# USB_HUB_schematic.net
KiCad netlist of a schematic drawn in EasyEDA Pro
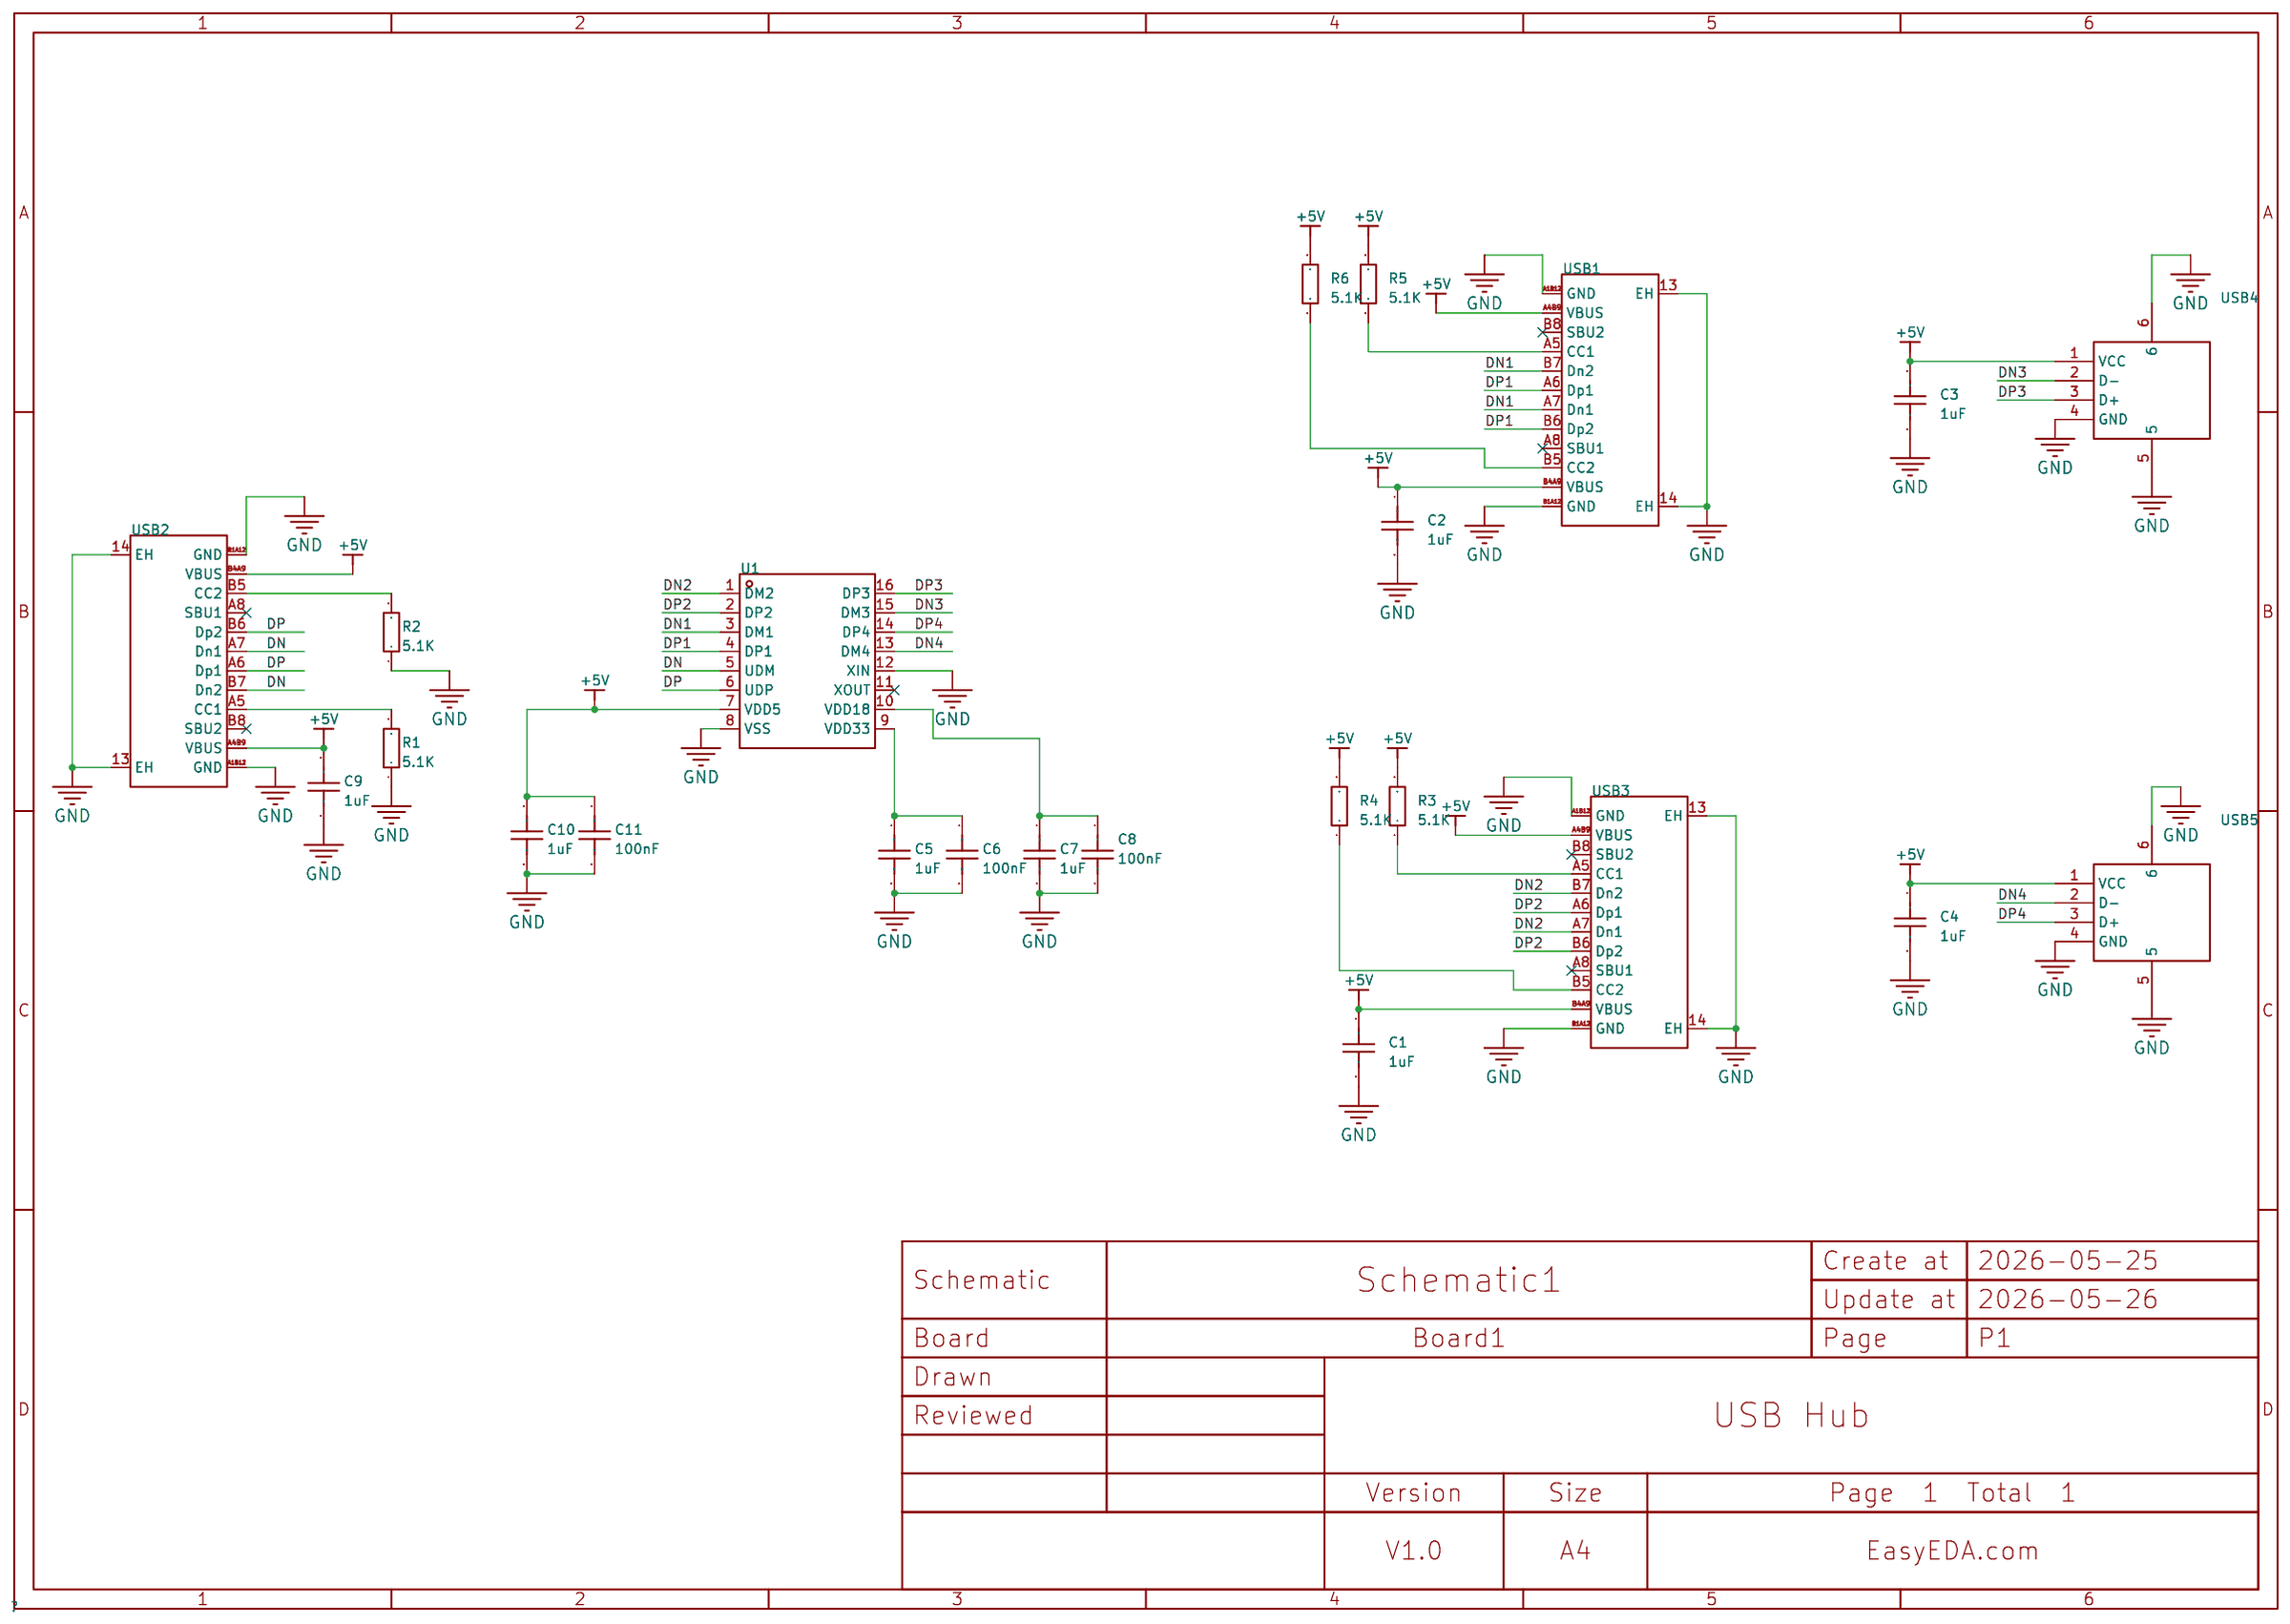
[diagram p0: schematic sheet]

(export (version "E")
  (design (tool "Eeschema 10.0.6"))
  (components
    (comp (ref "C1") (value "1uF") (footprint "easyedapro:C0603") (libsource (lib "easyedapro") (part "CAP")))
    (comp (ref "C2") (value "1uF") (footprint "easyedapro:C0603") (libsource (lib "easyedapro") (part "CAP")))
    (comp (ref "C3") (value "1uF") (footprint "easyedapro:C0603") (libsource (lib "easyedapro") (part "CAP")))
    (comp (ref "C4") (value "1uF") (footprint "easyedapro:C0603") (libsource (lib "easyedapro") (part "CAP")))
    (comp (ref "C5") (value "1uF") (footprint "easyedapro:C0603") (libsource (lib "easyedapro") (part "CAP")))
    (comp (ref "C6")
      (value "100nF")
      (footprint "easyedapro:C0603")
      (libsource (lib "easyedapro") (part "CAP"))
    )
    (comp (ref "C7") (value "1uF") (footprint "easyedapro:C0603") (libsource (lib "easyedapro") (part "CAP")))
    (comp (ref "C8")
      (value "100nF")
      (footprint "easyedapro:C0603")
      (libsource (lib "easyedapro") (part "CAP"))
    )
    (comp (ref "C9") (value "1uF") (footprint "easyedapro:C0603") (libsource (lib "easyedapro") (part "CAP")))
    (comp (ref "C10")
      (value "1uF")
      (footprint "easyedapro:C0603")
      (libsource (lib "easyedapro") (part "CAP"))
    )
    (comp (ref "C11")
      (value "100nF")
      (footprint "easyedapro:C0603")
      (libsource (lib "easyedapro") (part "CAP"))
    )
    (comp (ref "R1")
      (value "5.1K")
      (footprint "easyedapro:R0603")
      (libsource (lib "easyedapro") (part "Res"))
    )
    (comp (ref "R2")
      (value "5.1K")
      (footprint "easyedapro:R0603")
      (libsource (lib "easyedapro") (part "Res"))
    )
    (comp (ref "R3")
      (value "5.1K")
      (footprint "easyedapro:R0603")
      (libsource (lib "easyedapro") (part "Res"))
    )
    (comp (ref "R4")
      (value "5.1K")
      (footprint "easyedapro:R0603")
      (libsource (lib "easyedapro") (part "Res"))
    )
    (comp (ref "R5")
      (value "5.1K")
      (footprint "easyedapro:R0603")
      (libsource (lib "easyedapro") (part "Res"))
    )
    (comp (ref "R6")
      (value "5.1K")
      (footprint "easyedapro:R0603")
      (libsource (lib "easyedapro") (part "Res"))
    )
    (comp (ref "U1")
      (value "SL2.1s")
      (footprint "easyedapro:SSOP-16_L4.6-W2.6-P0.53-LS4.0-BL")
      (fields (field (name "Manufacturer") "CoreChips(和芯润德)"))
      (libsource (lib "easyedapro") (part "SL2.1S"))
    )
    (comp (ref "USB1")
      (value "TYPE-C 16PIN 2MD(073)")
      (footprint "easyedapro:USB-C-SMD_TYPE-C-16PIN-2MD-073")
      (fields (field (name "Manufacturer") "SHOU HAN(首韩)"))
      (libsource (lib "easyedapro") (part "TYPE-C 16PIN 2MD(073)"))
    )
    (comp (ref "USB2")
      (value "TYPE-C 16PIN 2MD(073)")
      (footprint "easyedapro:USB-C-SMD_TYPE-C-16PIN-2MD-073")
      (fields (field (name "Manufacturer") "SHOU HAN(首韩)"))
      (libsource (lib "easyedapro") (part "TYPE-C 16PIN 2MD(073)"))
    )
    (comp (ref "USB3")
      (value "TYPE-C 16PIN 2MD(073)")
      (footprint "easyedapro:USB-C-SMD_TYPE-C-16PIN-2MD-073")
      (fields (field (name "Manufacturer") "SHOU HAN(首韩)"))
      (libsource (lib "easyedapro") (part "TYPE-C 16PIN 2MD(073)"))
    )
    (comp (ref "USB4")
      (value "10.0 QHHTZB6.3")
      (footprint "easyedapro:USB-A-TH_10.0QHHTZB6.3")
      (fields (field (name "Manufacturer") "SHOU HAN(首韩)"))
      (libsource (lib "easyedapro") (part "10.0 QHHTZB6.3"))
    )
    (comp (ref "USB5")
      (value "10.0 QHHTZB6.3")
      (footprint "easyedapro:USB-A-TH_10.0QHHTZB6.3")
      (fields (field (name "Manufacturer") "SHOU HAN(首韩)"))
      (libsource (lib "easyedapro") (part "10.0 QHHTZB6.3"))
    )
  )
  (nets
    (net (code "1") (name "+5V") (class "Default")
      (node (ref "C1") (pin "1") (pinfunction "1_1") (pintype "input"))
      (node (ref "C10") (pin "1") (pinfunction "1_1") (pintype "input"))
      (node (ref "C11") (pin "1") (pinfunction "1_1") (pintype "input"))
      (node (ref "C2") (pin "1") (pinfunction "1_1") (pintype "input"))
      (node (ref "C3") (pin "1") (pinfunction "1_1") (pintype "input"))
      (node (ref "C4") (pin "1") (pinfunction "1_1") (pintype "input"))
      (node (ref "C9") (pin "1") (pinfunction "1_1") (pintype "input"))
      (node (ref "R3") (pin "2") (pinfunction "2_2") (pintype "input"))
      (node (ref "R4") (pin "2") (pinfunction "2_2") (pintype "input"))
      (node (ref "R5") (pin "2") (pinfunction "2_2") (pintype "input"))
      (node (ref "R6") (pin "2") (pinfunction "2_2") (pintype "input"))
      (node (ref "U1") (pin "7") (pinfunction "VDD5_7") (pintype "unspecified"))
      (node (ref "USB1") (pin "A4B9") (pinfunction "VBUS_A4B9") (pintype "unspecified"))
      (node (ref "USB1") (pin "B4A9") (pinfunction "VBUS_B4A9") (pintype "unspecified"))
      (node (ref "USB2") (pin "A4B9") (pinfunction "VBUS_A4B9") (pintype "unspecified"))
      (node (ref "USB2") (pin "B4A9") (pinfunction "VBUS_B4A9") (pintype "unspecified"))
      (node (ref "USB3") (pin "A4B9") (pinfunction "VBUS_A4B9") (pintype "unspecified"))
      (node (ref "USB3") (pin "B4A9") (pinfunction "VBUS_B4A9") (pintype "unspecified"))
      (node (ref "USB4") (pin "1") (pinfunction "VCC_1") (pintype "unspecified"))
      (node (ref "USB5") (pin "1") (pinfunction "VCC_1") (pintype "unspecified"))
    )
    (net (code "2") (name "/DN") (class "Default")
      (node (ref "U1") (pin "5") (pinfunction "UDM_5") (pintype "unspecified"))
      (node (ref "USB2") (pin "A7") (pinfunction "Dn1_A7") (pintype "unspecified"))
      (node (ref "USB2") (pin "B7") (pinfunction "Dn2_B7") (pintype "unspecified"))
    )
    (net (code "3") (name "/DN1") (class "Default")
      (node (ref "U1") (pin "3") (pinfunction "DM1_3") (pintype "unspecified"))
      (node (ref "USB1") (pin "A7") (pinfunction "Dn1_A7") (pintype "unspecified"))
      (node (ref "USB1") (pin "B7") (pinfunction "Dn2_B7") (pintype "unspecified"))
    )
    (net (code "4") (name "/DN2") (class "Default")
      (node (ref "U1") (pin "1") (pinfunction "DM2_1") (pintype "unspecified"))
      (node (ref "USB3") (pin "A7") (pinfunction "Dn1_A7") (pintype "unspecified"))
      (node (ref "USB3") (pin "B7") (pinfunction "Dn2_B7") (pintype "unspecified"))
    )
    (net (code "5") (name "/DN3") (class "Default")
      (node (ref "U1") (pin "15") (pinfunction "DM3_15") (pintype "unspecified"))
      (node (ref "USB4") (pin "2") (pinfunction "D-_2") (pintype "unspecified"))
    )
    (net (code "6") (name "/DN4") (class "Default")
      (node (ref "U1") (pin "13") (pinfunction "DM4_13") (pintype "unspecified"))
      (node (ref "USB5") (pin "2") (pinfunction "D-_2") (pintype "unspecified"))
    )
    (net (code "7") (name "/DP") (class "Default")
      (node (ref "U1") (pin "6") (pinfunction "UDP_6") (pintype "unspecified"))
      (node (ref "USB2") (pin "A6") (pinfunction "Dp1_A6") (pintype "unspecified"))
      (node (ref "USB2") (pin "B6") (pinfunction "Dp2_B6") (pintype "unspecified"))
    )
    (net (code "8") (name "/DP1") (class "Default")
      (node (ref "U1") (pin "4") (pinfunction "DP1_4") (pintype "unspecified"))
      (node (ref "USB1") (pin "A6") (pinfunction "Dp1_A6") (pintype "unspecified"))
      (node (ref "USB1") (pin "B6") (pinfunction "Dp2_B6") (pintype "unspecified"))
    )
    (net (code "9") (name "/DP2") (class "Default")
      (node (ref "U1") (pin "2") (pinfunction "DP2_2") (pintype "unspecified"))
      (node (ref "USB3") (pin "A6") (pinfunction "Dp1_A6") (pintype "unspecified"))
      (node (ref "USB3") (pin "B6") (pinfunction "Dp2_B6") (pintype "unspecified"))
    )
    (net (code "10") (name "/DP3") (class "Default")
      (node (ref "U1") (pin "16") (pinfunction "DP3_16") (pintype "unspecified"))
      (node (ref "USB4") (pin "3") (pinfunction "D+_3") (pintype "unspecified"))
    )
    (net (code "11") (name "/DP4") (class "Default")
      (node (ref "U1") (pin "14") (pinfunction "DP4_14") (pintype "unspecified"))
      (node (ref "USB5") (pin "3") (pinfunction "D+_3") (pintype "unspecified"))
    )
    (net (code "12") (name "GND") (class "Default")
      (node (ref "C1") (pin "2") (pinfunction "2_2") (pintype "input"))
      (node (ref "C10") (pin "2") (pinfunction "2_2") (pintype "input"))
      (node (ref "C11") (pin "2") (pinfunction "2_2") (pintype "input"))
      (node (ref "C2") (pin "2") (pinfunction "2_2") (pintype "input"))
      (node (ref "C3") (pin "2") (pinfunction "2_2") (pintype "input"))
      (node (ref "C4") (pin "2") (pinfunction "2_2") (pintype "input"))
      (node (ref "C5") (pin "2") (pinfunction "2_2") (pintype "input"))
      (node (ref "C6") (pin "2") (pinfunction "2_2") (pintype "input"))
      (node (ref "C7") (pin "2") (pinfunction "2_2") (pintype "input"))
      (node (ref "C8") (pin "2") (pinfunction "2_2") (pintype "input"))
      (node (ref "C9") (pin "2") (pinfunction "2_2") (pintype "input"))
      (node (ref "R1") (pin "1") (pinfunction "1_1") (pintype "input"))
      (node (ref "R2") (pin "1") (pinfunction "1_1") (pintype "input"))
      (node (ref "U1") (pin "12") (pinfunction "XIN_12") (pintype "unspecified"))
      (node (ref "U1") (pin "8") (pinfunction "VSS_8") (pintype "unspecified"))
      (node (ref "USB1") (pin "13") (pinfunction "EH_13") (pintype "unspecified"))
      (node (ref "USB1") (pin "14") (pinfunction "EH_14") (pintype "unspecified"))
      (node (ref "USB1") (pin "A1B12") (pinfunction "GND_A1B12") (pintype "unspecified"))
      (node (ref "USB1") (pin "B1A12") (pinfunction "GND_B1A12") (pintype "unspecified"))
      (node (ref "USB2") (pin "13") (pinfunction "EH_13") (pintype "unspecified"))
      (node (ref "USB2") (pin "14") (pinfunction "EH_14") (pintype "unspecified"))
      (node (ref "USB2") (pin "A1B12") (pinfunction "GND_A1B12") (pintype "unspecified"))
      (node (ref "USB2") (pin "B1A12") (pinfunction "GND_B1A12") (pintype "unspecified"))
      (node (ref "USB3") (pin "13") (pinfunction "EH_13") (pintype "unspecified"))
      (node (ref "USB3") (pin "14") (pinfunction "EH_14") (pintype "unspecified"))
      (node (ref "USB3") (pin "A1B12") (pinfunction "GND_A1B12") (pintype "unspecified"))
      (node (ref "USB3") (pin "B1A12") (pinfunction "GND_B1A12") (pintype "unspecified"))
      (node (ref "USB4") (pin "4") (pinfunction "GND_4") (pintype "unspecified"))
      (node (ref "USB4") (pin "5") (pinfunction "5_5") (pintype "unspecified"))
      (node (ref "USB4") (pin "6") (pinfunction "6_6") (pintype "unspecified"))
      (node (ref "USB5") (pin "4") (pinfunction "GND_4") (pintype "unspecified"))
      (node (ref "USB5") (pin "5") (pinfunction "5_5") (pintype "unspecified"))
      (node (ref "USB5") (pin "6") (pinfunction "6_6") (pintype "unspecified"))
    )
    (net (code "13") (name "Net-(U1-VDD18)") (class "Default")
      (node (ref "C7") (pin "1") (pinfunction "1_1") (pintype "input"))
      (node (ref "C8") (pin "1") (pinfunction "1_1") (pintype "input"))
      (node (ref "U1") (pin "10") (pinfunction "VDD18_10") (pintype "unspecified"))
    )
    (net (code "14") (name "Net-(U1-VDD33)") (class "Default")
      (node (ref "C5") (pin "1") (pinfunction "1_1") (pintype "input"))
      (node (ref "C6") (pin "1") (pinfunction "1_1") (pintype "input"))
      (node (ref "U1") (pin "9") (pinfunction "VDD33_9") (pintype "unspecified"))
    )
    (net (code "15") (name "Net-(USB1-CC1)") (class "Default")
      (node (ref "R5") (pin "1") (pinfunction "1_1") (pintype "input"))
      (node (ref "USB1") (pin "A5") (pinfunction "CC1_A5") (pintype "unspecified"))
    )
    (net (code "16") (name "Net-(USB1-CC2)") (class "Default")
      (node (ref "R6") (pin "1") (pinfunction "1_1") (pintype "input"))
      (node (ref "USB1") (pin "B5") (pinfunction "CC2_B5") (pintype "unspecified"))
    )
    (net (code "17") (name "Net-(USB2-CC1)") (class "Default")
      (node (ref "R1") (pin "2") (pinfunction "2_2") (pintype "input"))
      (node (ref "USB2") (pin "A5") (pinfunction "CC1_A5") (pintype "unspecified"))
    )
    (net (code "18") (name "Net-(USB2-CC2)") (class "Default")
      (node (ref "R2") (pin "2") (pinfunction "2_2") (pintype "input"))
      (node (ref "USB2") (pin "B5") (pinfunction "CC2_B5") (pintype "unspecified"))
    )
    (net (code "19") (name "Net-(USB3-CC1)") (class "Default")
      (node (ref "R3") (pin "1") (pinfunction "1_1") (pintype "input"))
      (node (ref "USB3") (pin "A5") (pinfunction "CC1_A5") (pintype "unspecified"))
    )
    (net (code "20") (name "Net-(USB3-CC2)") (class "Default")
      (node (ref "R4") (pin "1") (pinfunction "1_1") (pintype "input"))
      (node (ref "USB3") (pin "B5") (pinfunction "CC2_B5") (pintype "unspecified"))
    )
    (net (code "21") (name "unconnected-(U1-XOUT-Pad11)") (class "Default")
      (node (ref "U1") (pin "11") (pinfunction "XOUT_11") (pintype "unspecified+no_connect"))
    )
    (net (code "22") (name "unconnected-(USB1-SBU1-PadA8)") (class "Default")
      (node (ref "USB1") (pin "A8") (pinfunction "SBU1_A8") (pintype "unspecified+no_connect"))
    )
    (net (code "23") (name "unconnected-(USB1-SBU2-PadB8)") (class "Default")
      (node (ref "USB1") (pin "B8") (pinfunction "SBU2_B8") (pintype "unspecified+no_connect"))
    )
    (net (code "24") (name "unconnected-(USB2-SBU1-PadA8)") (class "Default")
      (node (ref "USB2") (pin "A8") (pinfunction "SBU1_A8") (pintype "unspecified+no_connect"))
    )
    (net (code "25") (name "unconnected-(USB2-SBU2-PadB8)") (class "Default")
      (node (ref "USB2") (pin "B8") (pinfunction "SBU2_B8") (pintype "unspecified+no_connect"))
    )
    (net (code "26") (name "unconnected-(USB3-SBU1-PadA8)") (class "Default")
      (node (ref "USB3") (pin "A8") (pinfunction "SBU1_A8") (pintype "unspecified+no_connect"))
    )
    (net (code "27") (name "unconnected-(USB3-SBU2-PadB8)") (class "Default")
      (node (ref "USB3") (pin "B8") (pinfunction "SBU2_B8") (pintype "unspecified+no_connect"))
    )
  )
)
